# MB1-Hed-r1_0.net
KiCad netlist of a schematic drawn in Altium Designer
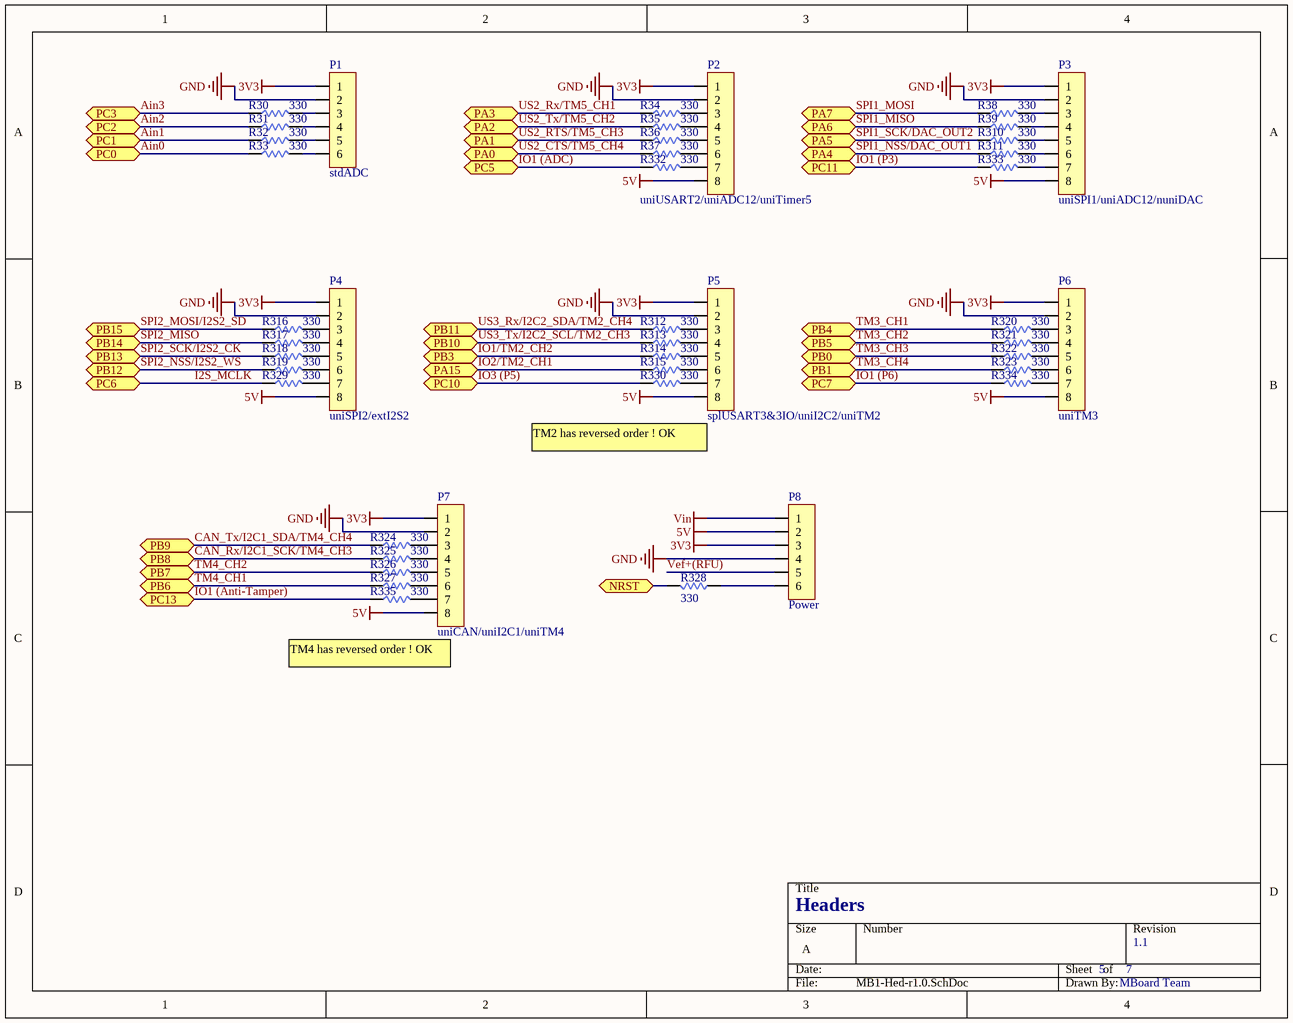
[diagram p0: MB1-Hed-r1.0.SchDoc]

(export (version "E")
  (design (tool "Eeschema 10.0.6"))
  (components
    (comp (ref "P1") (value "stdADC") (footprint "Hed6") (libsource (lib "MyLib") (part "Hed6")))
    (comp (ref "P2")
      (value "uniUSART2/uniADC12/uniTimer5")
      (footprint "Hed8")
      (libsource (lib "MyLib") (part "Hed8"))
    )
    (comp (ref "P3")
      (value "uniSPI1/uniADC12/nuniDAC")
      (footprint "Hed8")
      (libsource (lib "MyLib") (part "Hed8"))
    )
    (comp (ref "P4") (value "uniSPI2/extI2S2") (footprint "Hed8") (libsource (lib "MyLib") (part "Hed8")))
    (comp (ref "P5")
      (value "splUSART3&3IO/uniI2C2/uniTM2")
      (footprint "Hed8")
      (libsource (lib "MyLib") (part "Hed8"))
    )
    (comp (ref "P6") (value "uniTM3") (footprint "Hed8") (libsource (lib "MyLib") (part "Hed8")))
    (comp (ref "P7")
      (value "uniCAN/uniI2C1/uniTM4")
      (footprint "Hed8")
      (libsource (lib "MyLib") (part "Hed8"))
    )
    (comp (ref "P8") (value "Power") (footprint "Hed6") (libsource (lib "MyLib") (part "Hed6")))
    (comp (ref "R30")
      (value "330")
      (footprint "SM_0805_LD")
      (description "Resistor")
      (fields (field (name "Comment") "R") (field (name "PUBLISHER") "Altium Limited"))
      (libsource (lib "HLib_schematic_lib") (part "R"))
    )
    (comp (ref "R31")
      (value "330")
      (footprint "SM_0805_LD")
      (description "Resistor")
      (fields (field (name "Comment") "R") (field (name "PUBLISHER") "Altium Limited"))
      (libsource (lib "HLib_schematic_lib") (part "R"))
    )
    (comp (ref "R32")
      (value "330")
      (footprint "SM_0805_LD")
      (description "Resistor")
      (fields (field (name "Comment") "R") (field (name "PUBLISHER") "Altium Limited"))
      (libsource (lib "HLib_schematic_lib") (part "R"))
    )
    (comp (ref "R33")
      (value "330")
      (footprint "SM_0805_LD")
      (description "Resistor")
      (fields (field (name "Comment") "R") (field (name "PUBLISHER") "Altium Limited"))
      (libsource (lib "HLib_schematic_lib") (part "R"))
    )
    (comp (ref "R34")
      (value "330")
      (footprint "SM_0805_LD")
      (description "Resistor")
      (fields (field (name "Comment") "R") (field (name "PUBLISHER") "Altium Limited"))
      (libsource (lib "HLib_schematic_lib") (part "R"))
    )
    (comp (ref "R35")
      (value "330")
      (footprint "SM_0805_LD")
      (description "Resistor")
      (fields (field (name "Comment") "R") (field (name "PUBLISHER") "Altium Limited"))
      (libsource (lib "HLib_schematic_lib") (part "R"))
    )
    (comp (ref "R36")
      (value "330")
      (footprint "SM_0805_LD")
      (description "Resistor")
      (fields (field (name "Comment") "R") (field (name "PUBLISHER") "Altium Limited"))
      (libsource (lib "HLib_schematic_lib") (part "R"))
    )
    (comp (ref "R37")
      (value "330")
      (footprint "SM_0805_LD")
      (description "Resistor")
      (fields (field (name "Comment") "R") (field (name "PUBLISHER") "Altium Limited"))
      (libsource (lib "HLib_schematic_lib") (part "R"))
    )
    (comp (ref "R38")
      (value "330")
      (footprint "SM_0805_LD")
      (description "Resistor")
      (fields (field (name "Comment") "R") (field (name "PUBLISHER") "Altium Limited"))
      (libsource (lib "HLib_schematic_lib") (part "R"))
    )
    (comp (ref "R39")
      (value "330")
      (footprint "SM_0805_LD")
      (description "Resistor")
      (fields (field (name "Comment") "R") (field (name "PUBLISHER") "Altium Limited"))
      (libsource (lib "HLib_schematic_lib") (part "R"))
    )
    (comp (ref "R310")
      (value "330")
      (footprint "SM_0805_LD")
      (description "Resistor")
      (fields (field (name "Comment") "R") (field (name "PUBLISHER") "Altium Limited"))
      (libsource (lib "HLib_schematic_lib") (part "R"))
    )
    (comp (ref "R311")
      (value "330")
      (footprint "SM_0805_LD")
      (description "Resistor")
      (fields (field (name "Comment") "R") (field (name "PUBLISHER") "Altium Limited"))
      (libsource (lib "HLib_schematic_lib") (part "R"))
    )
    (comp (ref "R312")
      (value "330")
      (footprint "SM_0805_LD")
      (description "Resistor")
      (fields (field (name "Comment") "R") (field (name "PUBLISHER") "Altium Limited"))
      (libsource (lib "HLib_schematic_lib") (part "R"))
    )
    (comp (ref "R313")
      (value "330")
      (footprint "SM_0805_LD")
      (description "Resistor")
      (fields (field (name "Comment") "R") (field (name "PUBLISHER") "Altium Limited"))
      (libsource (lib "HLib_schematic_lib") (part "R"))
    )
    (comp (ref "R314")
      (value "330")
      (footprint "SM_0805_LD")
      (description "Resistor")
      (fields (field (name "Comment") "R") (field (name "PUBLISHER") "Altium Limited"))
      (libsource (lib "HLib_schematic_lib") (part "R"))
    )
    (comp (ref "R315")
      (value "330")
      (footprint "SM_0805_LD")
      (description "Resistor")
      (fields (field (name "Comment") "R") (field (name "PUBLISHER") "Altium Limited"))
      (libsource (lib "HLib_schematic_lib") (part "R"))
    )
    (comp (ref "R316")
      (value "330")
      (footprint "SM_0805_LD")
      (description "Resistor")
      (fields (field (name "Comment") "R") (field (name "PUBLISHER") "Altium Limited"))
      (libsource (lib "HLib_schematic_lib") (part "R"))
    )
    (comp (ref "R317")
      (value "330")
      (footprint "SM_0805_LD")
      (description "Resistor")
      (fields (field (name "Comment") "R") (field (name "PUBLISHER") "Altium Limited"))
      (libsource (lib "HLib_schematic_lib") (part "R"))
    )
    (comp (ref "R318")
      (value "330")
      (footprint "SM_0805_LD")
      (description "Resistor")
      (fields (field (name "Comment") "R") (field (name "PUBLISHER") "Altium Limited"))
      (libsource (lib "HLib_schematic_lib") (part "R"))
    )
    (comp (ref "R319")
      (value "330")
      (footprint "SM_0805_LD")
      (description "Resistor")
      (fields (field (name "Comment") "R") (field (name "PUBLISHER") "Altium Limited"))
      (libsource (lib "HLib_schematic_lib") (part "R"))
    )
    (comp (ref "R320")
      (value "330")
      (footprint "SM_0805_LD")
      (description "Resistor")
      (fields (field (name "Comment") "R") (field (name "PUBLISHER") "Altium Limited"))
      (libsource (lib "HLib_schematic_lib") (part "R"))
    )
    (comp (ref "R321")
      (value "330")
      (footprint "SM_0805_LD")
      (description "Resistor")
      (fields (field (name "Comment") "R") (field (name "PUBLISHER") "Altium Limited"))
      (libsource (lib "HLib_schematic_lib") (part "R"))
    )
    (comp (ref "R322")
      (value "330")
      (footprint "SM_0805_LD")
      (description "Resistor")
      (fields (field (name "Comment") "R") (field (name "PUBLISHER") "Altium Limited"))
      (libsource (lib "HLib_schematic_lib") (part "R"))
    )
    (comp (ref "R323")
      (value "330")
      (footprint "SM_0805_LD")
      (description "Resistor")
      (fields (field (name "Comment") "R") (field (name "PUBLISHER") "Altium Limited"))
      (libsource (lib "HLib_schematic_lib") (part "R"))
    )
    (comp (ref "R324")
      (value "330")
      (footprint "SM_0805_LD")
      (description "Resistor")
      (fields (field (name "Comment") "R") (field (name "PUBLISHER") "Altium Limited"))
      (libsource (lib "HLib_schematic_lib") (part "R"))
    )
    (comp (ref "R325")
      (value "330")
      (footprint "SM_0805_LD")
      (description "Resistor")
      (fields (field (name "Comment") "R") (field (name "PUBLISHER") "Altium Limited"))
      (libsource (lib "HLib_schematic_lib") (part "R"))
    )
    (comp (ref "R326")
      (value "330")
      (footprint "SM_0805_LD")
      (description "Resistor")
      (fields (field (name "Comment") "R") (field (name "PUBLISHER") "Altium Limited"))
      (libsource (lib "HLib_schematic_lib") (part "R"))
    )
    (comp (ref "R327")
      (value "330")
      (footprint "SM_0805_LD")
      (description "Resistor")
      (fields (field (name "Comment") "R") (field (name "PUBLISHER") "Altium Limited"))
      (libsource (lib "HLib_schematic_lib") (part "R"))
    )
    (comp (ref "R328")
      (value "330")
      (footprint "SM_0805_LD")
      (description "Resistor")
      (fields (field (name "Comment") "R") (field (name "PUBLISHER") "Altium Limited"))
      (libsource (lib "HLib_schematic_lib") (part "R"))
    )
    (comp (ref "R329")
      (value "330")
      (footprint "SM_0805_LD")
      (description "Resistor")
      (fields (field (name "Comment") "R") (field (name "PUBLISHER") "Altium Limited"))
      (libsource (lib "HLib_schematic_lib") (part "R"))
    )
    (comp (ref "R330")
      (value "330")
      (footprint "SM_0805_LD")
      (description "Resistor")
      (fields (field (name "Comment") "R") (field (name "PUBLISHER") "Altium Limited"))
      (libsource (lib "HLib_schematic_lib") (part "R"))
    )
    (comp (ref "R332")
      (value "330")
      (footprint "SM_0805_LD")
      (description "Resistor")
      (fields (field (name "Comment") "R") (field (name "PUBLISHER") "Altium Limited"))
      (libsource (lib "HLib_schematic_lib") (part "R"))
    )
    (comp (ref "R333")
      (value "330")
      (footprint "SM_0805_LD")
      (description "Resistor")
      (fields (field (name "Comment") "R") (field (name "PUBLISHER") "Altium Limited"))
      (libsource (lib "HLib_schematic_lib") (part "R"))
    )
    (comp (ref "R334")
      (value "330")
      (footprint "SM_0805_LD")
      (description "Resistor")
      (fields (field (name "Comment") "R") (field (name "PUBLISHER") "Altium Limited"))
      (libsource (lib "HLib_schematic_lib") (part "R"))
    )
    (comp (ref "R335")
      (value "330")
      (footprint "SM_0805_LD")
      (description "Resistor")
      (fields (field (name "Comment") "R") (field (name "PUBLISHER") "Altium Limited"))
      (libsource (lib "HLib_schematic_lib") (part "R"))
    )
  )
  (nets
    (net (code "1") (name "/Ain0") (class "Default")
      (node (ref "R33") (pin "1") (pinfunction "1_1") (pintype "passive"))
    )
    (net (code "2") (name "/Ain1") (class "Default")
      (node (ref "R32") (pin "1") (pinfunction "1_1") (pintype "passive"))
    )
    (net (code "3") (name "/Ain2") (class "Default")
      (node (ref "R31") (pin "1") (pinfunction "1_1") (pintype "passive"))
    )
    (net (code "4") (name "/Ain3") (class "Default")
      (node (ref "R30") (pin "1") (pinfunction "1_1") (pintype "passive"))
    )
    (net (code "5") (name "/CAN_Rx{slash}I2C1_SCK{slash}TM4_CH3") (class "Default")
      (node (ref "R325") (pin "1") (pinfunction "1_1") (pintype "passive"))
    )
    (net (code "6") (name "/CAN_Tx{slash}I2C1_SDA{slash}TM4_CH4") (class "Default")
      (node (ref "R324") (pin "1") (pinfunction "1_1") (pintype "passive"))
    )
    (net (code "7") (name "/I2S_MCLK") (class "Default")
      (node (ref "R329") (pin "1") (pinfunction "1_1") (pintype "passive"))
    )
    (net (code "8") (name "/IO1 (ADC)") (class "Default")
      (node (ref "R332") (pin "1") (pinfunction "1_1") (pintype "passive"))
    )
    (net (code "9") (name "/IO1 (Anti-Tamper)") (class "Default")
      (node (ref "R335") (pin "1") (pinfunction "1_1") (pintype "passive"))
    )
    (net (code "10") (name "/IO1 (P3)") (class "Default")
      (node (ref "R333") (pin "1") (pinfunction "1_1") (pintype "passive"))
    )
    (net (code "11") (name "/IO1 (P6)") (class "Default")
      (node (ref "R334") (pin "1") (pinfunction "1_1") (pintype "passive"))
    )
    (net (code "12") (name "/IO1{slash}TM2_CH2") (class "Default")
      (node (ref "R314") (pin "1") (pinfunction "1_1") (pintype "passive"))
    )
    (net (code "13") (name "/IO2{slash}TM2_CH1") (class "Default")
      (node (ref "R315") (pin "1") (pinfunction "1_1") (pintype "passive"))
    )
    (net (code "14") (name "/IO3 (P5)") (class "Default")
      (node (ref "R330") (pin "1") (pinfunction "1_1") (pintype "passive"))
    )
    (net (code "15") (name "/NRST") (class "Default")
      (node (ref "R328") (pin "1") (pinfunction "1_1") (pintype "passive"))
    )
    (net (code "16") (name "/SPI1_MISO") (class "Default")
      (node (ref "R39") (pin "1") (pinfunction "1_1") (pintype "passive"))
    )
    (net (code "17") (name "/SPI1_MOSI") (class "Default")
      (node (ref "R38") (pin "1") (pinfunction "1_1") (pintype "passive"))
    )
    (net (code "18") (name "/SPI1_NSS{slash}DAC_OUT1") (class "Default")
      (node (ref "R311") (pin "1") (pinfunction "1_1") (pintype "passive"))
    )
    (net (code "19") (name "/SPI1_SCK{slash}DAC_OUT2") (class "Default")
      (node (ref "R310") (pin "1") (pinfunction "1_1") (pintype "passive"))
    )
    (net (code "20") (name "/SPI2_MISO") (class "Default")
      (node (ref "R317") (pin "1") (pinfunction "1_1") (pintype "passive"))
    )
    (net (code "21") (name "/SPI2_MOSI{slash}I2S2_SD") (class "Default")
      (node (ref "R316") (pin "1") (pinfunction "1_1") (pintype "passive"))
    )
    (net (code "22") (name "/SPI2_NSS{slash}I2S2_WS") (class "Default")
      (node (ref "R319") (pin "1") (pinfunction "1_1") (pintype "passive"))
    )
    (net (code "23") (name "/SPI2_SCK{slash}I2S2_CK") (class "Default")
      (node (ref "R318") (pin "1") (pinfunction "1_1") (pintype "passive"))
    )
    (net (code "24") (name "/TM3_CH1") (class "Default")
      (node (ref "R320") (pin "1") (pinfunction "1_1") (pintype "passive"))
    )
    (net (code "25") (name "/TM3_CH2") (class "Default")
      (node (ref "R321") (pin "1") (pinfunction "1_1") (pintype "passive"))
    )
    (net (code "26") (name "/TM3_CH3") (class "Default")
      (node (ref "R322") (pin "1") (pinfunction "1_1") (pintype "passive"))
    )
    (net (code "27") (name "/TM3_CH4") (class "Default")
      (node (ref "R323") (pin "1") (pinfunction "1_1") (pintype "passive"))
    )
    (net (code "28") (name "/TM4_CH1") (class "Default")
      (node (ref "R327") (pin "1") (pinfunction "1_1") (pintype "passive"))
    )
    (net (code "29") (name "/TM4_CH2") (class "Default")
      (node (ref "R326") (pin "1") (pinfunction "1_1") (pintype "passive"))
    )
    (net (code "30") (name "/US2_CTS{slash}TM5_CH4") (class "Default")
      (node (ref "R37") (pin "1") (pinfunction "1_1") (pintype "passive"))
    )
    (net (code "31") (name "/US2_RTS{slash}TM5_CH3") (class "Default")
      (node (ref "R36") (pin "1") (pinfunction "1_1") (pintype "passive"))
    )
    (net (code "32") (name "/US2_Rx{slash}TM5_CH1") (class "Default")
      (node (ref "R34") (pin "1") (pinfunction "1_1") (pintype "passive"))
    )
    (net (code "33") (name "/US2_Tx{slash}TM5_CH2") (class "Default")
      (node (ref "R35") (pin "1") (pinfunction "1_1") (pintype "passive"))
    )
    (net (code "34") (name "/US3_Rx{slash}I2C2_SDA{slash}TM2_CH4") (class "Default")
      (node (ref "R312") (pin "1") (pinfunction "1_1") (pintype "passive"))
    )
    (net (code "35") (name "/US3_Tx{slash}I2C2_SCL{slash}TM2_CH3") (class "Default")
      (node (ref "R313") (pin "1") (pinfunction "1_1") (pintype "passive"))
    )
    (net (code "36") (name "/Vef+(RFU)") (class "Default")
      (node (ref "P8") (pin "5") (pinfunction "5_5") (pintype "passive"))
    )
    (net (code "37") (name "3V3") (class "Default")
      (node (ref "P1") (pin "1") (pinfunction "1_1") (pintype "passive"))
      (node (ref "P2") (pin "1") (pinfunction "1_1") (pintype "passive"))
      (node (ref "P3") (pin "1") (pinfunction "1_1") (pintype "passive"))
      (node (ref "P4") (pin "1") (pinfunction "1_1") (pintype "passive"))
      (node (ref "P5") (pin "1") (pinfunction "1_1") (pintype "passive"))
      (node (ref "P6") (pin "1") (pinfunction "1_1") (pintype "passive"))
      (node (ref "P7") (pin "1") (pinfunction "1_1") (pintype "passive"))
      (node (ref "P8") (pin "3") (pinfunction "3_3") (pintype "passive"))
    )
    (net (code "38") (name "5V") (class "Default")
      (node (ref "P2") (pin "8") (pinfunction "8_8") (pintype "passive"))
      (node (ref "P3") (pin "8") (pinfunction "8_8") (pintype "passive"))
      (node (ref "P4") (pin "8") (pinfunction "8_8") (pintype "passive"))
      (node (ref "P5") (pin "8") (pinfunction "8_8") (pintype "passive"))
      (node (ref "P6") (pin "8") (pinfunction "8_8") (pintype "passive"))
      (node (ref "P7") (pin "8") (pinfunction "8_8") (pintype "passive"))
      (node (ref "P8") (pin "2") (pinfunction "2_2") (pintype "passive"))
    )
    (net (code "39") (name "GND") (class "Default")
      (node (ref "P1") (pin "2") (pinfunction "2_2") (pintype "passive"))
      (node (ref "P2") (pin "2") (pinfunction "2_2") (pintype "passive"))
      (node (ref "P3") (pin "2") (pinfunction "2_2") (pintype "passive"))
      (node (ref "P4") (pin "2") (pinfunction "2_2") (pintype "passive"))
      (node (ref "P5") (pin "2") (pinfunction "2_2") (pintype "passive"))
      (node (ref "P6") (pin "2") (pinfunction "2_2") (pintype "passive"))
      (node (ref "P7") (pin "2") (pinfunction "2_2") (pintype "passive"))
      (node (ref "P8") (pin "4") (pinfunction "4_4") (pintype "passive"))
    )
    (net (code "40") (name "Net-(P1-Pad3)") (class "Default")
      (node (ref "P1") (pin "3") (pinfunction "3_3") (pintype "passive"))
      (node (ref "R30") (pin "2") (pinfunction "2_2") (pintype "passive"))
    )
    (net (code "41") (name "Net-(P1-Pad4)") (class "Default")
      (node (ref "P1") (pin "4") (pinfunction "4_4") (pintype "passive"))
      (node (ref "R31") (pin "2") (pinfunction "2_2") (pintype "passive"))
    )
    (net (code "42") (name "Net-(P1-Pad5)") (class "Default")
      (node (ref "P1") (pin "5") (pinfunction "5_5") (pintype "passive"))
      (node (ref "R32") (pin "2") (pinfunction "2_2") (pintype "passive"))
    )
    (net (code "43") (name "Net-(P1-Pad6)") (class "Default")
      (node (ref "P1") (pin "6") (pinfunction "6_6") (pintype "passive"))
      (node (ref "R33") (pin "2") (pinfunction "2_2") (pintype "passive"))
    )
    (net (code "44") (name "Net-(P2-Pad3)") (class "Default")
      (node (ref "P2") (pin "3") (pinfunction "3_3") (pintype "passive"))
      (node (ref "R34") (pin "2") (pinfunction "2_2") (pintype "passive"))
    )
    (net (code "45") (name "Net-(P2-Pad4)") (class "Default")
      (node (ref "P2") (pin "4") (pinfunction "4_4") (pintype "passive"))
      (node (ref "R35") (pin "2") (pinfunction "2_2") (pintype "passive"))
    )
    (net (code "46") (name "Net-(P2-Pad5)") (class "Default")
      (node (ref "P2") (pin "5") (pinfunction "5_5") (pintype "passive"))
      (node (ref "R36") (pin "2") (pinfunction "2_2") (pintype "passive"))
    )
    (net (code "47") (name "Net-(P2-Pad6)") (class "Default")
      (node (ref "P2") (pin "6") (pinfunction "6_6") (pintype "passive"))
      (node (ref "R37") (pin "2") (pinfunction "2_2") (pintype "passive"))
    )
    (net (code "48") (name "Net-(P2-Pad7)") (class "Default")
      (node (ref "P2") (pin "7") (pinfunction "7_7") (pintype "passive"))
      (node (ref "R332") (pin "2") (pinfunction "2_2") (pintype "passive"))
    )
    (net (code "49") (name "Net-(P3-Pad3)") (class "Default")
      (node (ref "P3") (pin "3") (pinfunction "3_3") (pintype "passive"))
      (node (ref "R38") (pin "2") (pinfunction "2_2") (pintype "passive"))
    )
    (net (code "50") (name "Net-(P3-Pad4)") (class "Default")
      (node (ref "P3") (pin "4") (pinfunction "4_4") (pintype "passive"))
      (node (ref "R39") (pin "2") (pinfunction "2_2") (pintype "passive"))
    )
    (net (code "51") (name "Net-(P3-Pad5)") (class "Default")
      (node (ref "P3") (pin "5") (pinfunction "5_5") (pintype "passive"))
      (node (ref "R310") (pin "2") (pinfunction "2_2") (pintype "passive"))
    )
    (net (code "52") (name "Net-(P3-Pad6)") (class "Default")
      (node (ref "P3") (pin "6") (pinfunction "6_6") (pintype "passive"))
      (node (ref "R311") (pin "2") (pinfunction "2_2") (pintype "passive"))
    )
    (net (code "53") (name "Net-(P3-Pad7)") (class "Default")
      (node (ref "P3") (pin "7") (pinfunction "7_7") (pintype "passive"))
      (node (ref "R333") (pin "2") (pinfunction "2_2") (pintype "passive"))
    )
    (net (code "54") (name "Net-(P4-Pad3)") (class "Default")
      (node (ref "P4") (pin "3") (pinfunction "3_3") (pintype "passive"))
      (node (ref "R316") (pin "2") (pinfunction "2_2") (pintype "passive"))
    )
    (net (code "55") (name "Net-(P4-Pad4)") (class "Default")
      (node (ref "P4") (pin "4") (pinfunction "4_4") (pintype "passive"))
      (node (ref "R317") (pin "2") (pinfunction "2_2") (pintype "passive"))
    )
    (net (code "56") (name "Net-(P4-Pad5)") (class "Default")
      (node (ref "P4") (pin "5") (pinfunction "5_5") (pintype "passive"))
      (node (ref "R318") (pin "2") (pinfunction "2_2") (pintype "passive"))
    )
    (net (code "57") (name "Net-(P4-Pad6)") (class "Default")
      (node (ref "P4") (pin "6") (pinfunction "6_6") (pintype "passive"))
      (node (ref "R319") (pin "2") (pinfunction "2_2") (pintype "passive"))
    )
    (net (code "58") (name "Net-(P4-Pad7)") (class "Default")
      (node (ref "P4") (pin "7") (pinfunction "7_7") (pintype "passive"))
      (node (ref "R329") (pin "2") (pinfunction "2_2") (pintype "passive"))
    )
    (net (code "59") (name "Net-(P5-Pad3)") (class "Default")
      (node (ref "P5") (pin "3") (pinfunction "3_3") (pintype "passive"))
      (node (ref "R312") (pin "2") (pinfunction "2_2") (pintype "passive"))
    )
    (net (code "60") (name "Net-(P5-Pad4)") (class "Default")
      (node (ref "P5") (pin "4") (pinfunction "4_4") (pintype "passive"))
      (node (ref "R313") (pin "2") (pinfunction "2_2") (pintype "passive"))
    )
    (net (code "61") (name "Net-(P5-Pad5)") (class "Default")
      (node (ref "P5") (pin "5") (pinfunction "5_5") (pintype "passive"))
      (node (ref "R314") (pin "2") (pinfunction "2_2") (pintype "passive"))
    )
    (net (code "62") (name "Net-(P5-Pad6)") (class "Default")
      (node (ref "P5") (pin "6") (pinfunction "6_6") (pintype "passive"))
      (node (ref "R315") (pin "2") (pinfunction "2_2") (pintype "passive"))
    )
    (net (code "63") (name "Net-(P5-Pad7)") (class "Default")
      (node (ref "P5") (pin "7") (pinfunction "7_7") (pintype "passive"))
      (node (ref "R330") (pin "2") (pinfunction "2_2") (pintype "passive"))
    )
    (net (code "64") (name "Net-(P6-Pad3)") (class "Default")
      (node (ref "P6") (pin "3") (pinfunction "3_3") (pintype "passive"))
      (node (ref "R320") (pin "2") (pinfunction "2_2") (pintype "passive"))
    )
    (net (code "65") (name "Net-(P6-Pad4)") (class "Default")
      (node (ref "P6") (pin "4") (pinfunction "4_4") (pintype "passive"))
      (node (ref "R321") (pin "2") (pinfunction "2_2") (pintype "passive"))
    )
    (net (code "66") (name "Net-(P6-Pad5)") (class "Default")
      (node (ref "P6") (pin "5") (pinfunction "5_5") (pintype "passive"))
      (node (ref "R322") (pin "2") (pinfunction "2_2") (pintype "passive"))
    )
    (net (code "67") (name "Net-(P6-Pad6)") (class "Default")
      (node (ref "P6") (pin "6") (pinfunction "6_6") (pintype "passive"))
      (node (ref "R323") (pin "2") (pinfunction "2_2") (pintype "passive"))
    )
    (net (code "68") (name "Net-(P6-Pad7)") (class "Default")
      (node (ref "P6") (pin "7") (pinfunction "7_7") (pintype "passive"))
      (node (ref "R334") (pin "2") (pinfunction "2_2") (pintype "passive"))
    )
    (net (code "69") (name "Net-(P7-Pad3)") (class "Default")
      (node (ref "P7") (pin "3") (pinfunction "3_3") (pintype "passive"))
      (node (ref "R324") (pin "2") (pinfunction "2_2") (pintype "passive"))
    )
    (net (code "70") (name "Net-(P7-Pad4)") (class "Default")
      (node (ref "P7") (pin "4") (pinfunction "4_4") (pintype "passive"))
      (node (ref "R325") (pin "2") (pinfunction "2_2") (pintype "passive"))
    )
    (net (code "71") (name "Net-(P7-Pad5)") (class "Default")
      (node (ref "P7") (pin "5") (pinfunction "5_5") (pintype "passive"))
      (node (ref "R326") (pin "2") (pinfunction "2_2") (pintype "passive"))
    )
    (net (code "72") (name "Net-(P7-Pad6)") (class "Default")
      (node (ref "P7") (pin "6") (pinfunction "6_6") (pintype "passive"))
      (node (ref "R327") (pin "2") (pinfunction "2_2") (pintype "passive"))
    )
    (net (code "73") (name "Net-(P7-Pad7)") (class "Default")
      (node (ref "P7") (pin "7") (pinfunction "7_7") (pintype "passive"))
      (node (ref "R335") (pin "2") (pinfunction "2_2") (pintype "passive"))
    )
    (net (code "74") (name "Net-(P8-Pad6)") (class "Default")
      (node (ref "P8") (pin "6") (pinfunction "6_6") (pintype "passive"))
      (node (ref "R328") (pin "2") (pinfunction "2_2") (pintype "passive"))
    )
    (net (code "75") (name "Vin") (class "Default")
      (node (ref "P8") (pin "1") (pinfunction "1_1") (pintype "passive"))
    )
  )
)
